# SCH_TRSID_2026-05-11.net
KiCad netlist of a schematic drawn in EasyEDA
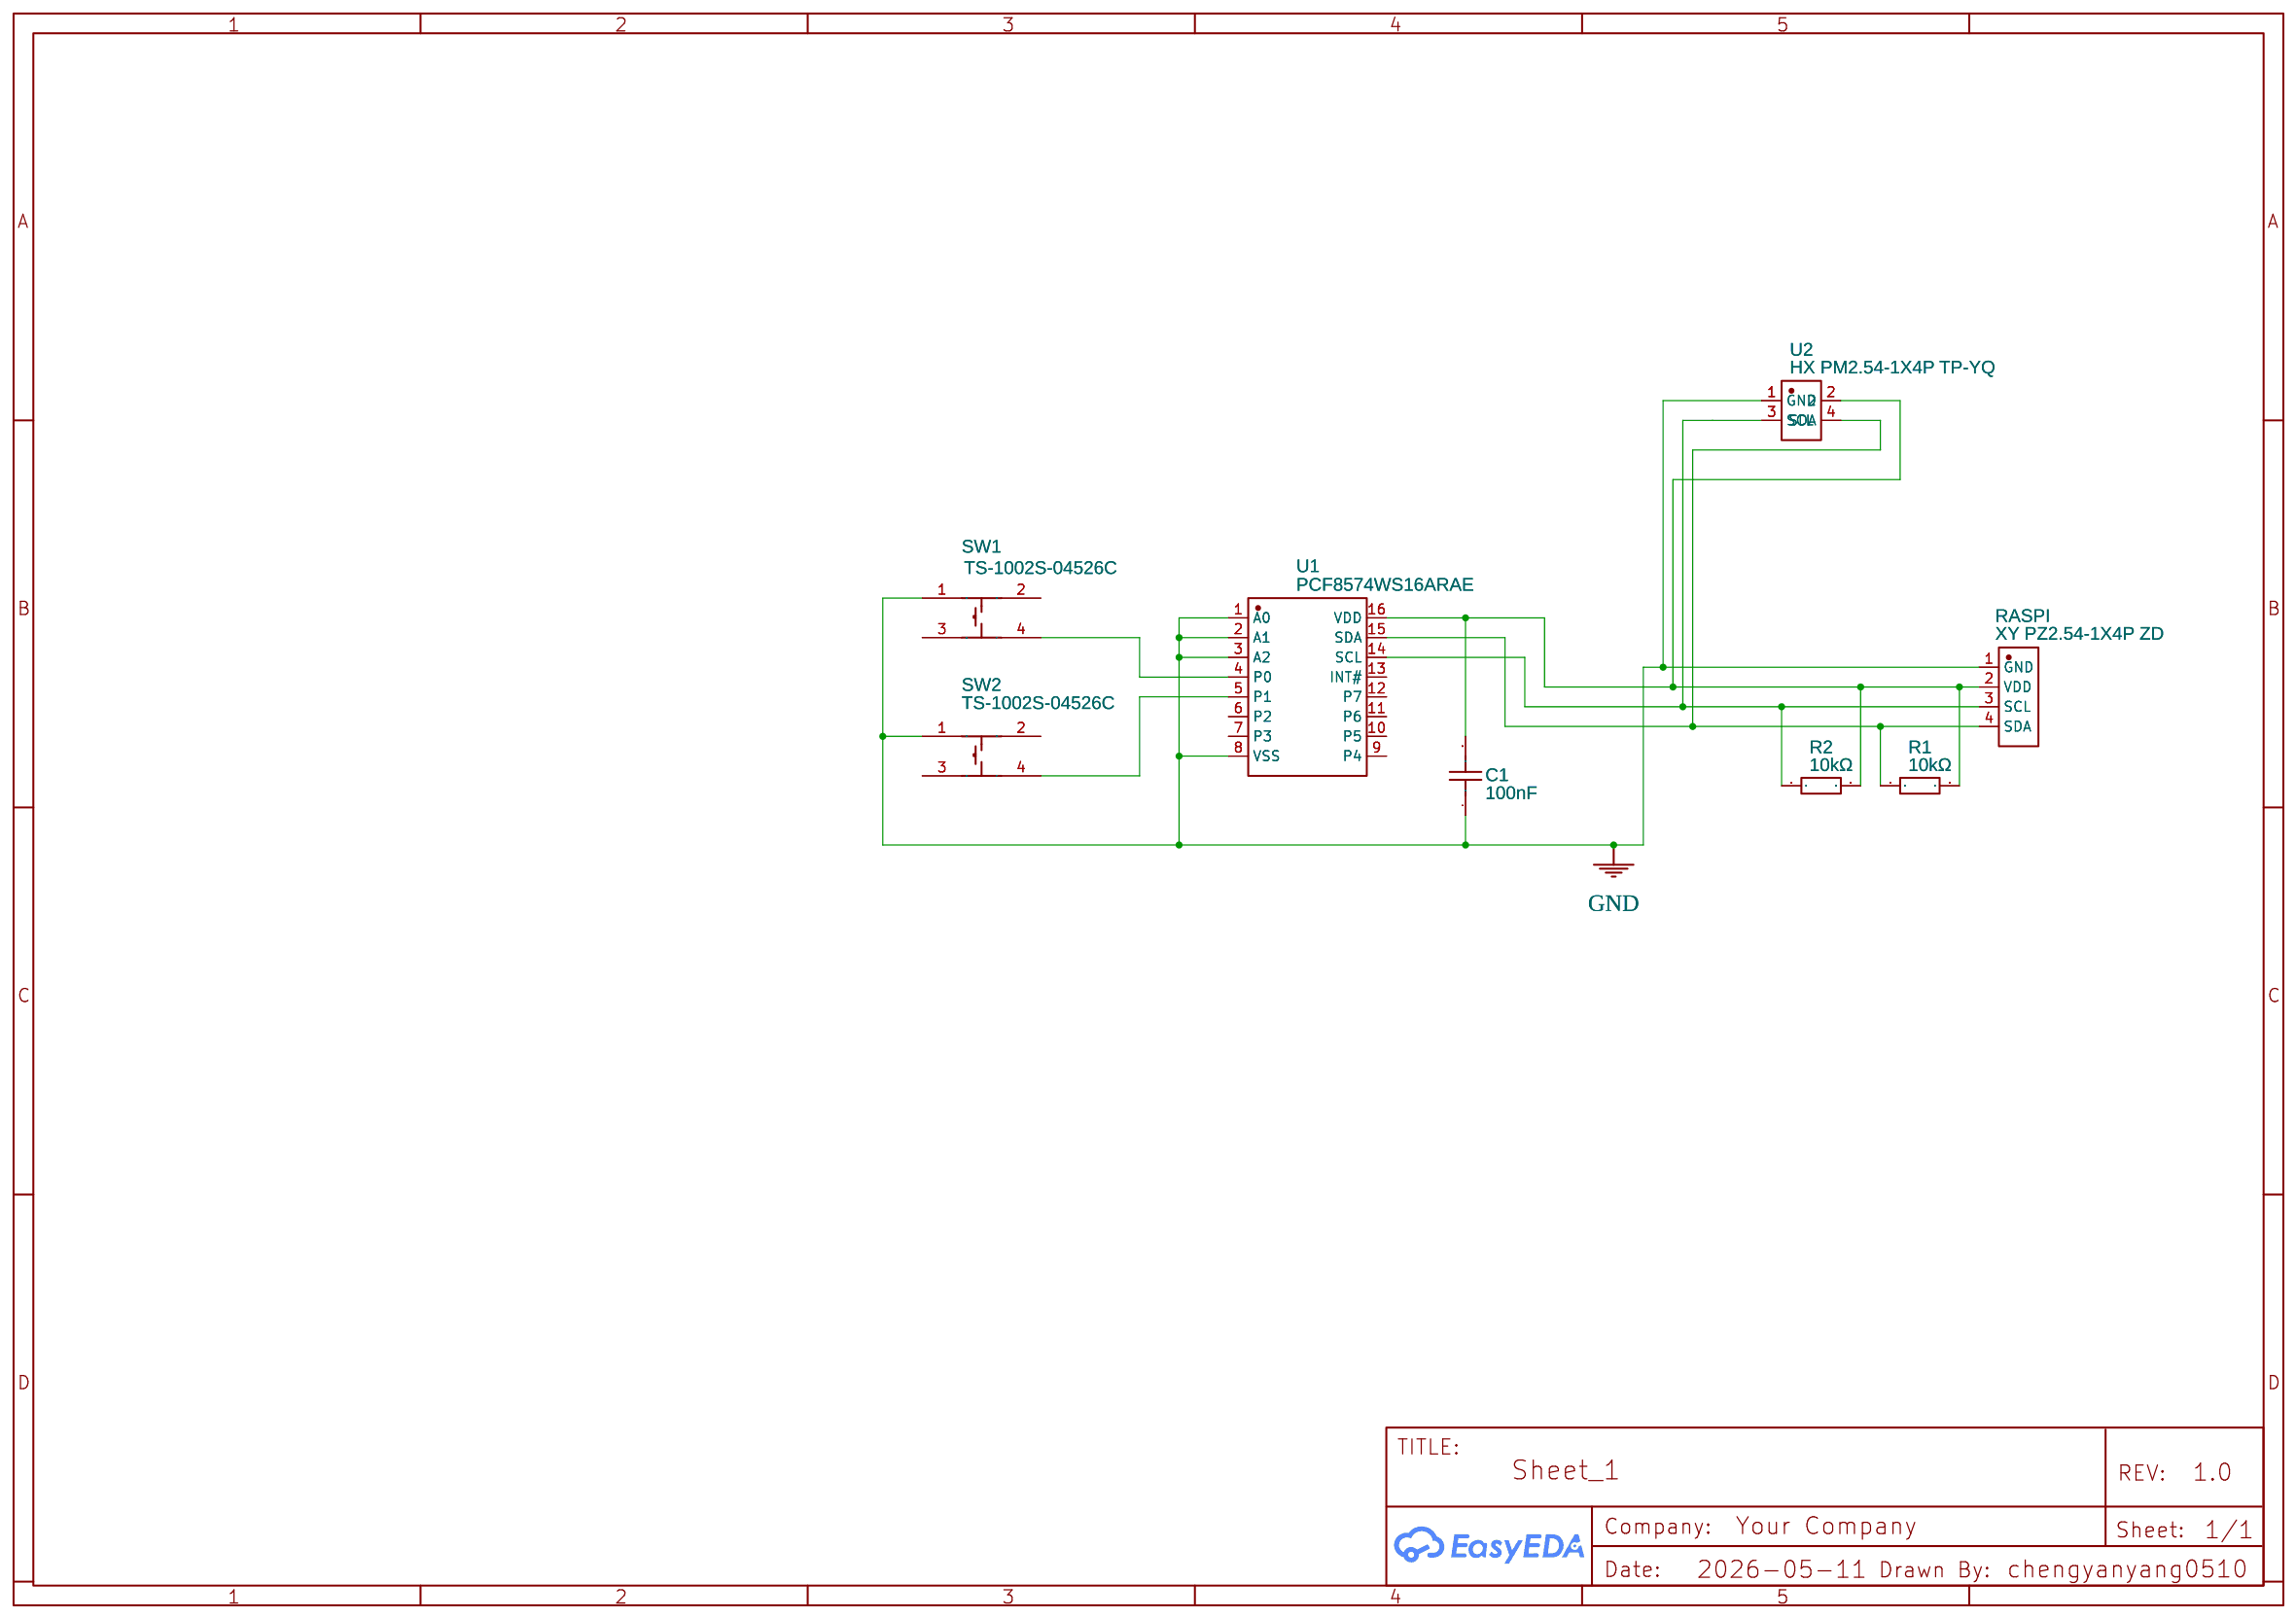
[diagram p0: schematic sheet]

(export (version "E")
  (design (tool "Eeschema 10.0.6"))
  (components
    (comp (ref "C1")
      (value "100nF")
      (fields
        (field (name "Manufacturer Part") "CL05B104KO5NNNC")
        (field (name "Manufacturer") "SAMSUNG(三星)")
      )
      (libsource (lib "") (part "CL05B104KO5NNNC"))
    )
    (comp (ref "R1")
      (value "10kΩ")
      (fields
        (field (name "Manufacturer Part") "1206W4F1002T5E")
        (field (name "Manufacturer") "UNI-ROYAL(厚声)")
      )
      (libsource (lib "") (part "1206W4F1002T5E"))
    )
    (comp (ref "R2")
      (value "10kΩ")
      (fields
        (field (name "Manufacturer Part") "1206W4F1002T5E")
        (field (name "Manufacturer") "UNI-ROYAL(厚声)")
      )
      (libsource (lib "") (part "1206W4F1002T5E"))
    )
    (comp (ref "RASPI")
      (value "XY PZ2.54-1X4P ZD")
      (fields
        (field (name "Manufacturer Part") "XY PZ2.54-1x4P ZD")
        (field (name "Manufacturer") "XYECONN(辛译)")
      )
      (libsource (lib "") (part "XY PZ2.54-1X4P ZD"))
    )
    (comp (ref "SW1")
      (value "TS-1002S-04526C")
      (fields (field (name "Manufacturer") "XUNPU(讯普)"))
      (libsource (lib "") (part "TS-1002S-04526C"))
    )
    (comp (ref "SW2")
      (value "TS-1002S-04526C")
      (fields (field (name "Manufacturer") "XUNPU(讯普)"))
      (libsource (lib "") (part "TS-1002S-04526C"))
    )
    (comp (ref "U1")
      (value "PCF8574WS16ARAE")
      (fields (field (name "Manufacturer") "GR(国睿)"))
      (libsource (lib "") (part "PCF8574WS16ARAE"))
    )
    (comp (ref "U2")
      (value "HX PM2.54-1X4P TP-YQ")
      (fields
        (field (name "Manufacturer Part") "HX PM2.54-1x4P TP-YQ")
        (field (name "Manufacturer") "hanxia(韩下)")
      )
      (libsource (lib "") (part "HX PM2.54-1X4P TP-YQ"))
    )
  )
  (nets
    (net (code "1") (name "GND") (class "Default")
      (node (ref "C1") (pin "1") (pinfunction "1_1") (pintype "unspecified"))
      (node (ref "RASPI") (pin "1") (pinfunction "GND_1") (pintype "unspecified"))
      (node (ref "SW1") (pin "1") (pinfunction "1_1") (pintype "unspecified"))
      (node (ref "SW2") (pin "1") (pinfunction "1_1") (pintype "unspecified"))
      (node (ref "U1") (pin "1") (pinfunction "A0_1") (pintype "unspecified"))
      (node (ref "U1") (pin "2") (pinfunction "A1_2") (pintype "unspecified"))
      (node (ref "U1") (pin "3") (pinfunction "A2_3") (pintype "unspecified"))
      (node (ref "U1") (pin "8") (pinfunction "VSS_8") (pintype "unspecified"))
      (node (ref "U2") (pin "1") (pinfunction "GND_1") (pintype "unspecified"))
    )
    (net (code "2") (name "Net-(RASPI-SCL)") (class "Default")
      (node (ref "R2") (pin "1") (pinfunction "1_1") (pintype "input"))
      (node (ref "RASPI") (pin "3") (pinfunction "SCL_3") (pintype "unspecified"))
      (node (ref "U1") (pin "14") (pinfunction "SCL_14") (pintype "unspecified"))
      (node (ref "U2") (pin "3") (pinfunction "SCL_3") (pintype "unspecified"))
    )
    (net (code "3") (name "Net-(RASPI-SDA)") (class "Default")
      (node (ref "R1") (pin "1") (pinfunction "1_1") (pintype "input"))
      (node (ref "RASPI") (pin "4") (pinfunction "SDA_4") (pintype "unspecified"))
      (node (ref "U1") (pin "15") (pinfunction "SDA_15") (pintype "unspecified"))
      (node (ref "U2") (pin "4") (pinfunction "SDA_4") (pintype "unspecified"))
    )
    (net (code "4") (name "Net-(RASPI-VDD)") (class "Default")
      (node (ref "C1") (pin "2") (pinfunction "2_2") (pintype "unspecified"))
      (node (ref "R1") (pin "2") (pinfunction "2_2") (pintype "input"))
      (node (ref "R2") (pin "2") (pinfunction "2_2") (pintype "input"))
      (node (ref "RASPI") (pin "2") (pinfunction "VDD_2") (pintype "unspecified"))
      (node (ref "U1") (pin "16") (pinfunction "VDD_16") (pintype "unspecified"))
      (node (ref "U2") (pin "2") (pinfunction "2_2") (pintype "unspecified"))
    )
    (net (code "5") (name "Net-(U1-P0)") (class "Default")
      (node (ref "SW1") (pin "4") (pinfunction "4_4") (pintype "unspecified"))
      (node (ref "U1") (pin "4") (pinfunction "P0_4") (pintype "unspecified"))
    )
    (net (code "6") (name "Net-(U1-P1)") (class "Default")
      (node (ref "SW2") (pin "4") (pinfunction "4_4") (pintype "unspecified"))
      (node (ref "U1") (pin "5") (pinfunction "P1_5") (pintype "unspecified"))
    )
    (net (code "7") (name "unconnected-(SW1-Pad2)") (class "Default")
      (node (ref "SW1") (pin "2") (pinfunction "2_2") (pintype "unspecified"))
    )
    (net (code "8") (name "unconnected-(SW1-Pad3)") (class "Default")
      (node (ref "SW1") (pin "3") (pinfunction "3_3") (pintype "unspecified"))
    )
    (net (code "9") (name "unconnected-(SW2-Pad2)") (class "Default")
      (node (ref "SW2") (pin "2") (pinfunction "2_2") (pintype "unspecified"))
    )
    (net (code "10") (name "unconnected-(SW2-Pad3)") (class "Default")
      (node (ref "SW2") (pin "3") (pinfunction "3_3") (pintype "unspecified"))
    )
    (net (code "11") (name "unconnected-(U1-INT#-Pad13)") (class "Default")
      (node (ref "U1") (pin "13") (pinfunction "INT#_13") (pintype "unspecified"))
    )
    (net (code "12") (name "unconnected-(U1-P2-Pad6)") (class "Default")
      (node (ref "U1") (pin "6") (pinfunction "P2_6") (pintype "unspecified"))
    )
    (net (code "13") (name "unconnected-(U1-P3-Pad7)") (class "Default")
      (node (ref "U1") (pin "7") (pinfunction "P3_7") (pintype "unspecified"))
    )
    (net (code "14") (name "unconnected-(U1-P4-Pad9)") (class "Default")
      (node (ref "U1") (pin "9") (pinfunction "P4_9") (pintype "unspecified"))
    )
    (net (code "15") (name "unconnected-(U1-P5-Pad10)") (class "Default")
      (node (ref "U1") (pin "10") (pinfunction "P5_10") (pintype "unspecified"))
    )
    (net (code "16") (name "unconnected-(U1-P6-Pad11)") (class "Default")
      (node (ref "U1") (pin "11") (pinfunction "P6_11") (pintype "unspecified"))
    )
    (net (code "17") (name "unconnected-(U1-P7-Pad12)") (class "Default")
      (node (ref "U1") (pin "12") (pinfunction "P7_12") (pintype "unspecified"))
    )
  )
)
